# YGL_Y1.net
KiCad netlist of a schematic drawn in Altium Designer
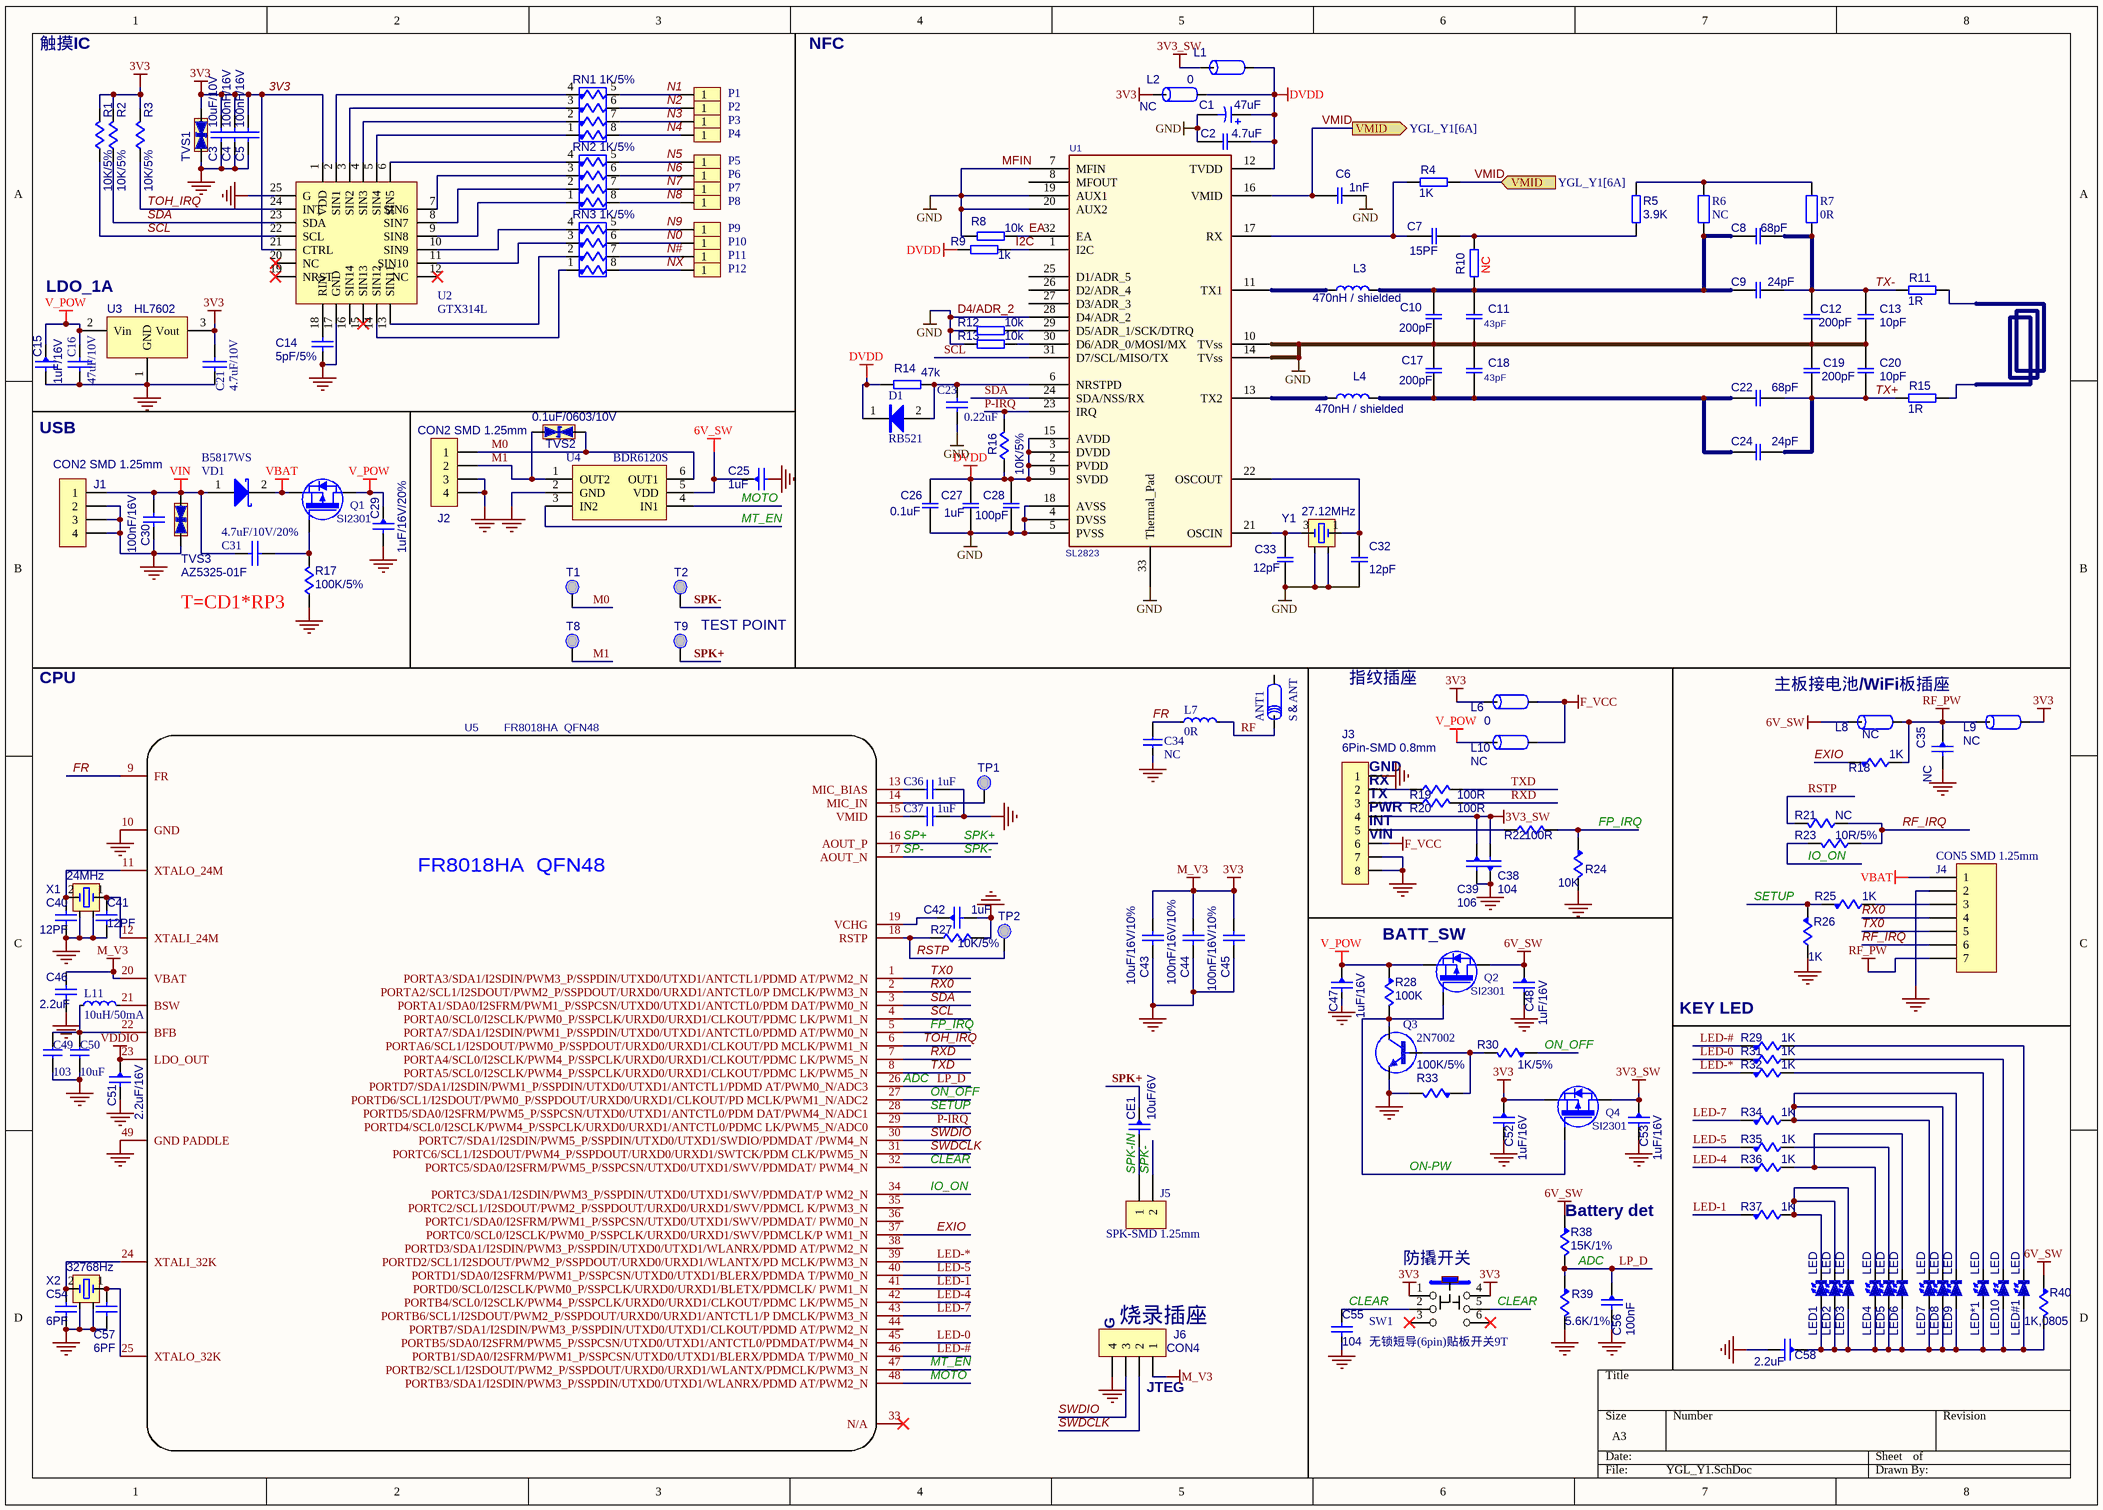
[diagram p0: YGL_Y1.SchDoc]

(export (version "E")
  (design (tool "Eeschema 10.0.6"))
  (components
    (comp (ref "ANT1") (value "S＆ANT") (footprint "ANT1206,SGM3157Y") (libsource (lib "TSL") (part "ANT")))
    (comp (ref "C1")
      (value "47uF")
      (footprint "C0603")
      (description "C_TANTAL_D")
      (fields (field (name "Comment") "330uF"))
      (libsource (lib "*") (part "C_TANTAL_D"))
    )
    (comp (ref "C2")
      (value "4.7uF")
      (footprint "C0603")
      (description "CAPC0603")
      (fields (field (name "Comment") "100nF"))
      (libsource (lib "*") (part "CAPC0603"))
    )
    (comp (ref "C3")
      (value "10uF/10V")
      (footprint "C0402")
      (description "Capacitor")
      (libsource (lib "") (part "CAP_1"))
    )
    (comp (ref "C4")
      (value "100nF/16V")
      (footprint "C0402")
      (description "Capacitor")
      (libsource (lib "") (part "CAP_1"))
    )
    (comp (ref "C5")
      (value "100nF/16V")
      (footprint "C0402")
      (description "Capacitor")
      (libsource (lib "") (part "CAP_1"))
    )
    (comp (ref "C6")
      (value "1nF")
      (footprint "C0402")
      (description "CAPC0603")
      (libsource (lib "*") (part "CAPC0603"))
    )
    (comp (ref "C7")
      (value "15PF")
      (footprint "C0402")
      (description "CAPC0805")
      (fields (field (name "Comment") "1nF"))
      (libsource (lib "*") (part "CAPC0805"))
    )
    (comp (ref "C8")
      (value "68pF")
      (footprint "C0402")
      (description "CAPC0805")
      (fields (field (name "Comment") "10pF"))
      (libsource (lib "*") (part "CAPC0805"))
    )
    (comp (ref "C9")
      (value "24pF")
      (footprint "C0402")
      (description "CAPC0805")
      (fields (field (name "Comment") "27pF"))
      (libsource (lib "*") (part "CAPC0805"))
    )
    (comp (ref "C10")
      (value "200pF")
      (footprint "C0402")
      (description "CAPC0805")
      (fields (field (name "Comment") "270pF"))
      (libsource (lib "*") (part "CAPC0805"))
    )
    (comp (ref "C11")
      (value "43pF")
      (footprint "C0402")
      (description "CAPC0805")
      (libsource (lib "*") (part "CAPC0805"))
    )
    (comp (ref "C12")
      (value "200pF")
      (footprint "C0402")
      (description "CAPC0805")
      (fields (field (name "Comment") "100pF"))
      (libsource (lib "*") (part "CAPC0805"))
    )
    (comp (ref "C13")
      (value "10pF")
      (footprint "C0402")
      (description "CAPC0805")
      (fields (field (name "Comment") "6pF"))
      (libsource (lib "*") (part "CAPC0805"))
    )
    (comp (ref "C14")
      (value "5pF/5%")
      (footprint "C0402")
      (description "Capacitor")
      (libsource (lib "") (part "CAP_1"))
    )
    (comp (ref "C15")
      (value "1uF/16V")
      (footprint "C0402")
      (description "Capacitor")
      (libsource (lib "VI-BC20X") (part "CAP"))
    )
    (comp (ref "C16")
      (value "47uF/10V")
      (footprint "C0402")
      (description "Capacitor")
      (libsource (lib "*") (part "CAP"))
    )
    (comp (ref "C17")
      (value "200pF")
      (footprint "C0402")
      (description "CAPC0805")
      (fields (field (name "Comment") "270pF"))
      (libsource (lib "*") (part "CAPC0805"))
    )
    (comp (ref "C18")
      (value "43pF")
      (footprint "C0402")
      (description "CAPC0805")
      (libsource (lib "*") (part "CAPC0805"))
    )
    (comp (ref "C19")
      (value "200pF")
      (footprint "C0402")
      (description "CAPC0805")
      (fields (field (name "Comment") "100pF"))
      (libsource (lib "*") (part "CAPC0805"))
    )
    (comp (ref "C20")
      (value "10pF")
      (footprint "C0402")
      (description "CAPC0805")
      (fields (field (name "Comment") "6pF"))
      (libsource (lib "*") (part "CAPC0805"))
    )
    (comp (ref "C21")
      (value "4.7uF/10V")
      (footprint "C0402")
      (description "Capacitor")
      (libsource (lib "*") (part "CAP"))
    )
    (comp (ref "C22")
      (value "68pF")
      (footprint "C0402")
      (description "CAPC0805")
      (fields (field (name "Comment") "27pF"))
      (libsource (lib "*") (part "CAPC0805"))
    )
    (comp (ref "C23")
      (value "0.22uF")
      (footprint "C0402")
      (description "Capacitor")
      (fields (field (name "Comment") "Cap") (field (name "PUBLISHER") "Altium Limited"))
      (libsource (lib "*") (part "Cap"))
    )
    (comp (ref "C24")
      (value "24pF")
      (footprint "C0402")
      (description "CAPC0805")
      (fields (field (name "Comment") "12pF"))
      (libsource (lib "*") (part "CAPC0805"))
    )
    (comp (ref "C25")
      (value "1uF")
      (footprint "C0402")
      (description "Capacitor")
      (libsource (lib "VI-BC20X") (part "CAP"))
    )
    (comp (ref "C26")
      (value "0.1uF")
      (footprint "C0402")
      (description "CAPC0603")
      (fields (field (name "Comment") "100nF"))
      (libsource (lib "*") (part "CAPC0603"))
    )
    (comp (ref "C27")
      (value "1uF")
      (footprint "C0402")
      (description "CAPC0603")
      (fields (field (name "Comment") "100nF"))
      (libsource (lib "*") (part "CAPC0603"))
    )
    (comp (ref "C28")
      (value "100pF")
      (footprint "C0402")
      (description "CAPC0603")
      (libsource (lib "*") (part "CAPC0603"))
    )
    (comp (ref "C29")
      (value "1uF/16V/20%")
      (footprint "C0402")
      (description "Capacitor")
      (libsource (lib "VI-BC20X") (part "CAP"))
    )
    (comp (ref "C30")
      (value "100nF/16V")
      (footprint "C0402")
      (description "Capacitor")
      (libsource (lib "") (part "CAP_1"))
    )
    (comp (ref "C31")
      (value "4.7uF/10V/20%")
      (footprint "C0402")
      (description "Capacitor")
      (libsource (lib "*") (part "CAP"))
    )
    (comp (ref "C32")
      (value "12pF")
      (footprint "C0402")
      (description "CAPC0603")
      (libsource (lib "*") (part "CAPC0603"))
    )
    (comp (ref "C33")
      (value "12pF")
      (footprint "C0402")
      (description "CAPC0603")
      (libsource (lib "*") (part "CAPC0603"))
    )
    (comp (ref "C34")
      (value "NC")
      (footprint "C0402")
      (description "Capacitor, NP0, ㊣5%")
      (fields (field (name "PART NUMBER") "C0402-0.8p") (field (name "PUBLISHER") "Nordic Semiconductor"))
      (libsource (lib "Nordic Passive DB") (part "CAP"))
    )
    (comp (ref "C35")
      (value "NC")
      (footprint "C0402")
      (description "Capacitor")
      (libsource (lib "VI-BC20X") (part "CAP"))
    )
    (comp (ref "C36")
      (value "1uF")
      (footprint "C0402")
      (description "Capacitor, NP0, ㊣5%")
      (fields (field (name "PART NUMBER") "C0402-0.8p") (field (name "PUBLISHER") "Nordic Semiconductor"))
      (libsource (lib "Nordic Passive DB") (part "CAP"))
    )
    (comp (ref "C37")
      (value "1uF")
      (footprint "C0402")
      (description "Capacitor, NP0, ㊣5%")
      (fields (field (name "PART NUMBER") "C0402-0.8p") (field (name "PUBLISHER") "Nordic Semiconductor"))
      (libsource (lib "Nordic Passive DB") (part "CAP"))
    )
    (comp (ref "C38")
      (value "104")
      (footprint "C0402")
      (description "Capacitor")
      (libsource (lib "VI-BC20X") (part "CAP"))
    )
    (comp (ref "C39")
      (value "106")
      (footprint "C0402")
      (description "Capacitor")
      (libsource (lib "VI-BC20X") (part "CAP"))
    )
    (comp (ref "C40")
      (value "12PF")
      (footprint "C0402")
      (description "Capacitor")
      (fields (field (name "PUBLISHER") "Altium Limited"))
      (libsource (lib "Miscellaneous Devices") (part "Cap"))
    )
    (comp (ref "C41")
      (value "12PF")
      (footprint "C0402")
      (description "Capacitor")
      (fields (field (name "PUBLISHER") "Altium Limited"))
      (libsource (lib "Miscellaneous Devices") (part "Cap"))
    )
    (comp (ref "C42")
      (value "1uF")
      (footprint "C0402")
      (description "Capacitor")
      (libsource (lib "VI-BC20X") (part "CAP"))
    )
    (comp (ref "C43")
      (value "10uF/16V/10%")
      (footprint "C0402")
      (description "Capacitor")
      (libsource (lib "") (part "CAP_1"))
    )
    (comp (ref "C44")
      (value "100nF/16V/10%")
      (footprint "C0402")
      (description "Capacitor")
      (libsource (lib "") (part "CAP_1"))
    )
    (comp (ref "C45")
      (value "100nF/16V/10%")
      (footprint "C0402")
      (description "Capacitor")
      (libsource (lib "") (part "CAP_1"))
    )
    (comp (ref "C46")
      (value "2.2uF")
      (footprint "C0402")
      (description "Capacitor")
      (fields (field (name "PUBLISHER") "Altium Limited"))
      (libsource (lib "Miscellaneous Devices") (part "Cap"))
    )
    (comp (ref "C47")
      (value "1uF/16V")
      (footprint "C0402")
      (description "Capacitor")
      (libsource (lib "VI-BC20X") (part "CAP"))
    )
    (comp (ref "C48")
      (value "1uF/16V")
      (footprint "C0402")
      (description "Capacitor")
      (libsource (lib "VI-BC20X") (part "CAP"))
    )
    (comp (ref "C49")
      (value "103")
      (footprint "C0402")
      (description "Capacitor, NP0, ㊣5%")
      (fields (field (name "PART NUMBER") "C0402-0.8p") (field (name "PUBLISHER") "Nordic Semiconductor"))
      (libsource (lib "Nordic Passive DB") (part "CAP"))
    )
    (comp (ref "C50")
      (value "10uF")
      (footprint "C0402")
      (description "Capacitor, NP0, ㊣5%")
      (fields (field (name "PART NUMBER") "C0402-0.8p") (field (name "PUBLISHER") "Nordic Semiconductor"))
      (libsource (lib "Nordic Passive DB") (part "CAP"))
    )
    (comp (ref "C51")
      (value "2.2uF/16V")
      (footprint "C0402")
      (description "Capacitor")
      (libsource (lib "VI-BC20X") (part "CAP"))
    )
    (comp (ref "C52")
      (value "1uF/16V")
      (footprint "C0402")
      (description "Capacitor")
      (libsource (lib "VI-BC20X") (part "CAP"))
    )
    (comp (ref "C53")
      (value "1uF/16V")
      (footprint "C0402")
      (description "Capacitor")
      (libsource (lib "VI-BC20X") (part "CAP"))
    )
    (comp (ref "C54")
      (value "6PF")
      (footprint "C0402")
      (description "Capacitor")
      (fields (field (name "PUBLISHER") "Altium Limited"))
      (libsource (lib "Miscellaneous Devices") (part "Cap"))
    )
    (comp (ref "C55")
      (value "104")
      (footprint "C0402")
      (description "Capacitor")
      (libsource (lib "") (part "CAP_1"))
    )
    (comp (ref "C56")
      (value "100nF")
      (footprint "C0402")
      (description "Capacitor")
      (libsource (lib "VI-BC20X") (part "CAP"))
    )
    (comp (ref "C57")
      (value "6PF")
      (footprint "C0402")
      (description "Capacitor")
      (fields (field (name "PUBLISHER") "Altium Limited"))
      (libsource (lib "Miscellaneous Devices") (part "Cap"))
    )
    (comp (ref "C58")
      (value "2.2uF")
      (footprint "C0402")
      (description "Capacitor")
      (libsource (lib "VI-BC20X") (part "CAP"))
    )
    (comp (ref "CE1")
      (value "10uF/6V")
      (footprint "C0402")
      (description "Capacitor")
      (libsource (lib "VI-BC20X") (part "CAP"))
    )
    (comp (ref "D1") (value "RB521") (footprint "SOD923") (libsource (lib "*") (part "DIODE-S")))
    (comp (ref "J1")
      (value "CON2 SMD 1.25mm")
      (footprint "SMD 1.25 2P")
      (description "Connector")
      (libsource (lib "NL-FLL00") (part "CON4"))
    )
    (comp (ref "J2")
      (value "CON2 SMD 1.25mm")
      (footprint "SMD 1.25 2P")
      (description "Connector")
      (libsource (lib "ND20D3") (part "CON4"))
    )
    (comp (ref "J3")
      (value "6Pin-SMD 0.8mm")
      (footprint "SMD 0.80 6P")
      (libsource (lib "TSL-600k-NFC触摸") (part "CON8"))
    )
    (comp (ref "J4")
      (value "CON5 SMD 1.25mm")
      (footprint "SMD 1.25 7P")
      (description "Header, 7-Pin")
      (fields (field (name "PUBLISHER") "Altium Limited"))
      (libsource (lib "Miscellaneous Connectors") (part "Header 7"))
    )
    (comp (ref "J5")
      (value "SPK-SMD 1.25mm")
      (footprint "SMD 1.25 2P")
      (description "Connector")
      (libsource (lib "*") (part "CON2"))
    )
    (comp (ref "J6")
      (value "CON4")
      (footprint "SMD 1.25 4p")
      (description "Connector")
      (libsource (lib "") (part "CON4_1"))
    )
    (comp (ref "L1") (value "0") (footprint "L0603") (libsource (lib "*") (part "FB")))
    (comp (ref "L2") (value "NC") (footprint "L0603") (libsource (lib "*") (part "FB")))
    (comp (ref "L3")
      (value "470nH / shielded")
      (footprint "L0603")
      (description "INDC1812")
      (fields (field (name "Comment") "470nH / shielded (1210)"))
      (libsource (lib "*") (part "INDC1812"))
    )
    (comp (ref "L4")
      (value "470nH / shielded")
      (footprint "L0603")
      (description "INDC1812")
      (fields (field (name "Comment") "470nH / shielded (1210)"))
      (libsource (lib "*") (part "INDC1812"))
    )
    (comp (ref "L6") (value "0") (footprint "L0603") (libsource (lib "*") (part "FB")))
    (comp (ref "L7")
      (value "0R")
      (footprint "L0603")
      (description "High frequency chip inductor ㊣5%")
      (fields (field (name "PART NUMBER") "L0402-3n9") (field (name "PUBLISHER") "Nordic Semiconductor"))
      (libsource (lib "Nordic Passive DB") (part "IND"))
    )
    (comp (ref "L8") (value "NC") (footprint "L0603") (libsource (lib "*") (part "FB")))
    (comp (ref "L9") (value "NC") (footprint "L0603") (libsource (lib "*") (part "FB")))
    (comp (ref "L10") (value "NC") (footprint "L0603") (libsource (lib "*") (part "FB")))
    (comp (ref "L11")
      (value "10uH/50mA")
      (footprint "L0603")
      (description "High frequency chip inductor ㊣5%")
      (fields (field (name "PART NUMBER") "L0402-3n9") (field (name "PUBLISHER") "Nordic Semiconductor"))
      (libsource (lib "Nordic Passive DB") (part "IND"))
    )
    (comp (ref "LED#1") (value "LED") (footprint "LED/1206") (libsource (lib "SCH") (part "LED")))
    (comp (ref "LED*1") (value "LED") (footprint "LED/1206") (libsource (lib "SCH") (part "LED")))
    (comp (ref "LED1") (value "LED") (footprint "LED/1206") (libsource (lib "SCH") (part "LED")))
    (comp (ref "LED2") (value "LED") (footprint "LED/1206") (libsource (lib "SCH") (part "LED")))
    (comp (ref "LED3") (value "LED") (footprint "LED/1206") (libsource (lib "SCH") (part "LED")))
    (comp (ref "LED4") (value "LED") (footprint "LED/1206") (libsource (lib "SCH") (part "LED")))
    (comp (ref "LED5") (value "LED") (footprint "LED/1206") (libsource (lib "SCH") (part "LED")))
    (comp (ref "LED6") (value "LED") (footprint "LED/1206") (libsource (lib "SCH") (part "LED")))
    (comp (ref "LED7") (value "LED") (footprint "LED/1206") (libsource (lib "SCH") (part "LED")))
    (comp (ref "LED8") (value "LED") (footprint "LED/1206") (libsource (lib "SCH") (part "LED")))
    (comp (ref "LED9") (value "LED") (footprint "LED/1206") (libsource (lib "SCH") (part "LED")))
    (comp (ref "LED10") (value "LED") (footprint "LED/1206") (libsource (lib "SCH") (part "LED")))
    (comp (ref "P1")
      (value "CON1")
      (footprint "TEST 0.8")
      (description "Connector")
      (libsource (lib "*") (part "CON1"))
    )
    (comp (ref "P2")
      (value "CON1")
      (footprint "TEST 0.8")
      (description "Connector")
      (libsource (lib "*") (part "CON1"))
    )
    (comp (ref "P3")
      (value "CON1")
      (footprint "TEST 0.8")
      (description "Connector")
      (libsource (lib "*") (part "CON1"))
    )
    (comp (ref "P4")
      (value "CON1")
      (footprint "TEST 0.8")
      (description "Connector")
      (libsource (lib "*") (part "CON1"))
    )
    (comp (ref "P5")
      (value "CON1")
      (footprint "TEST 0.8")
      (description "Connector")
      (libsource (lib "*") (part "CON1"))
    )
    (comp (ref "P6")
      (value "CON1")
      (footprint "TEST 0.8")
      (description "Connector")
      (libsource (lib "*") (part "CON1"))
    )
    (comp (ref "P7")
      (value "CON1")
      (footprint "TEST 0.8")
      (description "Connector")
      (libsource (lib "*") (part "CON1"))
    )
    (comp (ref "P8")
      (value "CON1")
      (footprint "TEST 0.8")
      (description "Connector")
      (libsource (lib "*") (part "CON1"))
    )
    (comp (ref "P9")
      (value "CON1")
      (footprint "TEST 0.8")
      (description "Connector")
      (libsource (lib "*") (part "CON1"))
    )
    (comp (ref "P10")
      (value "CON1")
      (footprint "TEST 0.8")
      (description "Connector")
      (libsource (lib "*") (part "CON1"))
    )
    (comp (ref "P11")
      (value "CON1")
      (footprint "TEST 0.8")
      (description "Connector")
      (libsource (lib "*") (part "CON1"))
    )
    (comp (ref "P12")
      (value "CON1")
      (footprint "TEST 0.8")
      (description "Connector")
      (libsource (lib "*") (part "CON1"))
    )
    (comp (ref "Q1")
      (value "SI2301")
      (footprint "SOT-23-3_L2.9-W1.6-P1.90-LS2.8-BR")
      (libsource (lib "NL-FLL19A _V1.0") (part "MOSFET-P"))
    )
    (comp (ref "Q2")
      (value "SI2301")
      (footprint "SOT-23-3_L2.9-W1.6-P1.90-LS2.8-BR")
      (libsource (lib "NL-FLL19A _V1.0") (part "MOSFET-P"))
    )
    (comp (ref "Q3")
      (value "2N7002")
      (footprint "SOT-23-3_L2.9-W1.6-P1.90-LS2.8-BR")
      (libsource (lib "*") (part "NPN"))
    )
    (comp (ref "Q4")
      (value "SI2301")
      (footprint "SOT-23-3_L2.9-W1.6-P1.90-LS2.8-BR")
      (libsource (lib "NL-FLL19A _V1.0") (part "MOSFET-P"))
    )
    (comp (ref "R1") (value "10K/5%") (footprint "R0402") (libsource (lib "NL-FLL00") (part "RES1")))
    (comp (ref "R2") (value "10K/5%") (footprint "R0402") (libsource (lib "NL-FLL00") (part "RES1")))
    (comp (ref "R3") (value "10K/5%") (footprint "R0402") (libsource (lib "NL-FLL00") (part "RES1")))
    (comp (ref "R4")
      (value "1K")
      (footprint "R0402")
      (description "RESC0805")
      (fields (field (name "Comment") "160R"))
      (libsource (lib "*") (part "RESC0805"))
    )
    (comp (ref "R5")
      (value "3.9K")
      (footprint "R0402")
      (description "RESC0805")
      (fields (field (name "Comment") "2k4"))
      (libsource (lib "*") (part "RESC0805"))
    )
    (comp (ref "R6")
      (value "16.9")
      (footprint "R0402")
      (description "0")
      (fields (field (name "ALTIUM_UNNAMED_1") "NC") (field (name "PUBLISHER") "Altium Limited"))
      (libsource (lib "ETC-Test1-1") (part "Res2"))
    )
    (comp (ref "R7")
      (value "16.9")
      (footprint "R0402")
      (description "0")
      (fields (field (name "ALTIUM_UNNAMED_1") "0R") (field (name "PUBLISHER") "Altium Limited"))
      (libsource (lib "ETC-Test1-1") (part "Res2"))
    )
    (comp (ref "R8")
      (value "10k")
      (footprint "R0402")
      (description "RESC0805")
      (libsource (lib "*") (part "RESC0805"))
    )
    (comp (ref "R9")
      (value "1k")
      (footprint "R0402")
      (description "RESC0805")
      (fields (field (name "Comment") "10k"))
      (libsource (lib "*") (part "RESC0805"))
    )
    (comp (ref "R10")
      (value "NC")
      (footprint "R0402")
      (description "RESC0805")
      (libsource (lib "*") (part "RESC0805"))
    )
    (comp (ref "R11")
      (value "1R")
      (footprint "R0402")
      (description "RESC0805")
      (fields (field (name "Comment") "160R"))
      (libsource (lib "*") (part "RESC0805"))
    )
    (comp (ref "R12")
      (value "10k")
      (footprint "R0402")
      (description "RESC0805")
      (libsource (lib "*") (part "RESC0805"))
    )
    (comp (ref "R13")
      (value "10k")
      (footprint "R0402")
      (description "RESC0805")
      (libsource (lib "*") (part "RESC0805"))
    )
    (comp (ref "R14")
      (value "47k")
      (footprint "R0402")
      (description "RESC0805")
      (fields (field (name "Comment") "10k"))
      (libsource (lib "*") (part "RESC0805"))
    )
    (comp (ref "R15")
      (value "1R")
      (footprint "R0402")
      (description "RESC0805")
      (fields (field (name "Comment") "160R"))
      (libsource (lib "*") (part "RESC0805"))
    )
    (comp (ref "R16") (value "10K/5%") (footprint "R0402") (libsource (lib "NL-FLL00") (part "RES1")))
    (comp (ref "R17") (value "100K/5%") (footprint "R0402") (libsource (lib "NL-FLL00") (part "RES1")))
    (comp (ref "R18") (value "1K") (footprint "R0402") (libsource (lib "智能拉手门禁_V2.0") (part "RES1")))
    (comp (ref "R19") (value "100R") (footprint "R0402") (libsource (lib "NL-FLL00") (part "RES1")))
    (comp (ref "R20") (value "100R") (footprint "R0402") (libsource (lib "NL-FLL00") (part "RES1")))
    (comp (ref "R21") (value "NC") (footprint "R0402") (libsource (lib "NL-FLL00") (part "RES1")))
    (comp (ref "R22") (value "100R") (footprint "R0402") (libsource (lib "NL-FLL00") (part "RES1")))
    (comp (ref "R23") (value "10R/5%") (footprint "R0402") (libsource (lib "NL-FLL00") (part "RES1")))
    (comp (ref "R24") (value "10K") (footprint "R0402") (libsource (lib "智能拉手门禁_V2.0") (part "RES1")))
    (comp (ref "R25") (value "1K") (footprint "R0402") (libsource (lib "智能拉手门禁_V2.0") (part "RES1")))
    (comp (ref "R26") (value "1K") (footprint "R0402") (libsource (lib "智能拉手门禁_V2.0") (part "RES1")))
    (comp (ref "R27") (value "10K/5%") (footprint "R0402") (libsource (lib "NL-FLL00") (part "RES1")))
    (comp (ref "R28") (value "100K") (footprint "R0402") (libsource (lib "智能拉手门禁_V2.0") (part "RES1")))
    (comp (ref "R29") (value "1K") (footprint "R0402") (libsource (lib "智能拉手门禁_V2.0") (part "RES1")))
    (comp (ref "R30") (value "1K/5%") (footprint "R0402") (libsource (lib "智能拉手门禁_V2.0") (part "RES1")))
    (comp (ref "R31") (value "1K") (footprint "R0402") (libsource (lib "智能拉手门禁_V2.0") (part "RES1")))
    (comp (ref "R32") (value "1K") (footprint "R0402") (libsource (lib "智能拉手门禁_V2.0") (part "RES1")))
    (comp (ref "R33") (value "100K/5%") (footprint "R0402") (libsource (lib "智能拉手门禁_V2.0") (part "RES1")))
    (comp (ref "R34") (value "1K") (footprint "R0402") (libsource (lib "智能拉手门禁_V2.0") (part "RES1")))
    (comp (ref "R35") (value "1K") (footprint "R0402") (libsource (lib "智能拉手门禁_V2.0") (part "RES1")))
    (comp (ref "R36") (value "1K") (footprint "R0402") (libsource (lib "智能拉手门禁_V2.0") (part "RES1")))
    (comp (ref "R37") (value "1K") (footprint "R0402") (libsource (lib "智能拉手门禁_V2.0") (part "RES1")))
    (comp (ref "R38") (value "15K/1%") (footprint "R0402") (libsource (lib "智能拉手门禁_V2.0") (part "RES1")))
    (comp (ref "R39") (value "5.6K/1%") (footprint "R0402") (libsource (lib "智能拉手门禁_V2.0") (part "RES1")))
    (comp (ref "R40") (value "1K,0805") (footprint "R0402") (libsource (lib "智能拉手门禁_V2.0") (part "RES1")))
    (comp (ref "RN1")
      (value "1K/5%")
      (footprint "R4D02")
      (libsource (lib "VI-LSX0X(拉手门禁)_V2.0") (part "8P4R-0603"))
    )
    (comp (ref "RN2")
      (value "1K/5%")
      (footprint "R4D02")
      (libsource (lib "VI-LSX0X(拉手门禁)_V2.0") (part "8P4R-0603"))
    )
    (comp (ref "RN3")
      (value "1K/5%")
      (footprint "R4D02")
      (libsource (lib "VI-LSX0X(拉手门禁)_V2.0") (part "8P4R-0603"))
    )
    (comp (ref "SW1")
      (value "无锁短导(6pin)贴板开关9T")
      (footprint "SW-6P-5.8X5.8_SMD")
      (libsource (lib "PCD3D_ID811B") (part "SW-4T"))
    )
    (comp (ref "T1")
      (value "~")
      (footprint "TEST 0.8")
      (description "Capacitor")
      (libsource (lib "*") (part "TX"))
    )
    (comp (ref "T2")
      (value "~")
      (footprint "TEST 0.8")
      (description "Capacitor")
      (libsource (lib "*") (part "TX"))
    )
    (comp (ref "T8")
      (value "~")
      (footprint "TEST 0.8")
      (description "Capacitor")
      (libsource (lib "*") (part "TX"))
    )
    (comp (ref "T9")
      (value "~")
      (footprint "TEST 0.8")
      (description "Capacitor")
      (libsource (lib "*") (part "TX"))
    )
    (comp (ref "TP1")
      (value "~")
      (footprint "TEST 0.8")
      (description "Capacitor")
      (libsource (lib "*") (part "TX"))
    )
    (comp (ref "TP2")
      (value "~")
      (footprint "TEST 0.8")
      (description "Capacitor")
      (libsource (lib "*") (part "TX"))
    )
    (comp (ref "TVS1")
      (value "AZ5325-01F")
      (footprint "SOD-323_L1.8-W1.3-LS2.5-RD")
      (libsource (lib "NL-FLL19D") (part "ESD"))
    )
    (comp (ref "TVS2")
      (value "0.1uF/0603/10V")
      (footprint "SOD-323_L1.8-W1.3-LS2.5-RD")
      (libsource (lib "") (part "ESD_1"))
    )
    (comp (ref "TVS3")
      (value "AZ5325-01F")
      (footprint "SOD-323_L1.8-W1.3-LS2.5-RD")
      (libsource (lib "NL-FLL19D") (part "ESD"))
    )
    (comp (ref "U1")
      (value "SL2823")
      (footprint "Z_QFN50P500X500X100-32N")
      (description "SL2523")
      (libsource (lib "ETC-Test1-1") (part "SL2523"))
    )
    (comp (ref "U2")
      (value "GTX314L")
      (footprint "QFN24_0.5 - U2")
      (libsource (lib "NL-FLL19C") (part "GTX314L"))
    )
    (comp (ref "U3")
      (value "HL7602")
      (footprint "SOT-89_L4.5-W2.5-P1.50-LS4.2-BR")
      (libsource (lib "*") (part "VOLTREG_4P"))
    )
    (comp (ref "U4")
      (value "BDR6120S")
      (footprint "SOT-23-6_L2.9-W1.6-P0.95-LS2.8-BL")
      (libsource (lib "*") (part "MX116L"))
    )
    (comp (ref "U5")
      (value "FR8018HA  QFN48")
      (footprint "QFN48_6*6*0.75_P0.4")
      (fields (field (name "CONTRIBUTOR") "liaobin123"))
      (libsource (lib "altium-import") (part "root_0_FR8018HA  QFN48_"))
    )
    (comp (ref "VD1")
      (value "B5817WS")
      (footprint "SOD-323_L1.8-W1.3-LS2.5-RD")
      (libsource (lib "*") (part "RB521"))
    )
    (comp (ref "X1")
      (value "24MHz")
      (footprint "XTAL-3225-SMT-A")
      (libsource (lib "SCH_1") (part "CRYSTAL_4PIN"))
    )
    (comp (ref "X2")
      (value "32768Hz")
      (footprint "XTAL_FC-135$2F$3215")
      (libsource (lib "SCH_1") (part "CRYSTAL_4PIN"))
    )
    (comp (ref "Y1")
      (value "27.12MHz")
      (footprint "XTAL-3225-SMT-A")
      (libsource (lib "NM810A_R1") (part "CRYSTAL_4PIN"))
    )
  )
  (nets
    (net (code "1") (name "/ADC") (class "Default")
      (node (ref "C56") (pin "1") (pinfunction "1_1") (pintype "passive"))
      (node (ref "R38") (pin "2") (pinfunction "2_2") (pintype "passive"))
      (node (ref "R39") (pin "1") (pinfunction "1_1") (pintype "passive"))
      (node (ref "U5") (pin "26") (pinfunction "PORTD7/SDA1/I2SDIN/PWM1_P/SSPDIN/UTXD0/UTXD1/ANTCTL1/PDMD_AT/PWM0_N/ADC3_26") (pintype "passive"))
    )
    (net (code "2") (name "/CLEAR") (class "Default")
      (node (ref "C55") (pin "1") (pinfunction "1_1") (pintype "passive"))
      (node (ref "SW1") (pin "2") (pinfunction "2_2") (pintype "passive"))
      (node (ref "SW1") (pin "5") (pinfunction "5_5") (pintype "passive"))
      (node (ref "U5") (pin "32") (pinfunction "PORTC5/SDA0/I2SFRM/PWM5_P/SSPCSN/UTXD0/UTXD1/SWV/PDMDAT/_PWM4_N_32") (pintype "passive"))
    )
    (net (code "3") (name "/EA") (class "Default")
      (node (ref "R8") (pin "2") (pintype "passive"))
      (node (ref "U1") (pin "32") (pinfunction "EA_32") (pintype "passive"))
    )
    (net (code "4") (name "/EXIO") (class "Default")
      (node (ref "R18") (pin "1") (pinfunction "1_1") (pintype "passive"))
      (node (ref "U5") (pin "37") (pinfunction "PORTC0/SCL0/I2SCLK/PWM0_P/SSPCLK/URXD0/URXD1/SWV/PDMCLK/P_WM1_N_37") (pintype "passive"))
    )
    (net (code "5") (name "/FP_IRQ") (class "Default")
      (node (ref "R22") (pin "1") (pinfunction "1_1") (pintype "passive"))
      (node (ref "R24") (pin "1") (pinfunction "1_1") (pintype "passive"))
      (node (ref "U5") (pin "5") (pinfunction "PORTA7/SDA1/I2SDIN/PWM1_P/SSPDIN/UTXD0/UTXD1/ANTCTL0/PDMD_AT/PWM0_N_5") (pintype "passive"))
    )
    (net (code "6") (name "/FR") (class "Default")
      (node (ref "C34") (pin "2") (pinfunction "2_2") (pintype "passive"))
      (node (ref "L7") (pin "1") (pinfunction "1_1") (pintype "passive"))
      (node (ref "U5") (pin "9") (pinfunction "FR_9") (pintype "passive"))
    )
    (net (code "7") (name "/I2C") (class "Default")
      (node (ref "R9") (pin "2") (pintype "passive"))
      (node (ref "U1") (pin "1") (pinfunction "I2C_1") (pintype "passive"))
    )
    (net (code "8") (name "/IO_ON") (class "Default")
      (node (ref "R23") (pin "2") (pinfunction "2_2") (pintype "passive"))
      (node (ref "U5") (pin "34") (pinfunction "PORTC3/SDA1/I2SDIN/PWM3_P/SSPDIN/UTXD0/UTXD1/SWV/PDMDAT/P_WM2_N_34") (pintype "passive"))
    )
    (net (code "9") (name "/LED-#") (class "Default")
      (node (ref "R29") (pin "1") (pinfunction "1_1") (pintype "passive"))
      (node (ref "U5") (pin "46") (pinfunction "PORTB1/SDA0/I2SFRM/PWM1_P/SSPCSN/UTXD0/UTXD1/BLERX/PDMDA_T/PWM0_N_46") (pintype "passive"))
    )
    (net (code "10") (name "/LED-*") (class "Default")
      (node (ref "R32") (pin "1") (pinfunction "1_1") (pintype "passive"))
      (node (ref "U5") (pin "39") (pinfunction "PORTD2/SCL1/I2SDOUT/PWM2_P/SSPDOUT/URXD0/URXD1/WLANTX/PD_MCLK/PWM3_N_39") (pintype "passive"))
    )
    (net (code "11") (name "/LED-0") (class "Default")
      (node (ref "R31") (pin "1") (pinfunction "1_1") (pintype "passive"))
      (node (ref "U5") (pin "45") (pinfunction "PORTB5/SDA0/I2SFRM/PWM5_P/SSPCSN/UTXD0/UTXD1/ANTCTL0/PDMDAT/PWM4_N_45") (pintype "passive"))
    )
    (net (code "12") (name "/LED-1") (class "Default")
      (node (ref "R37") (pin "1") (pinfunction "1_1") (pintype "passive"))
      (node (ref "U5") (pin "41") (pinfunction "PORTD0/SCL0/I2SCLK/PWM0_P/SSPCLK/URXD0/URXD1/BLETX/PDMCLK/_PWM1_N_41") (pintype "passive"))
    )
    (net (code "13") (name "/LED-4") (class "Default")
      (node (ref "R36") (pin "1") (pinfunction "1_1") (pintype "passive"))
      (node (ref "U5") (pin "42") (pinfunction "PORTB4/SCL0/I2SCLK/PWM4_P/SSPCLK/URXD0/URXD1/CLKOUT/PDMC_LK/PWM5_N_42") (pintype "passive"))
    )
    (net (code "14") (name "/LED-5") (class "Default")
      (node (ref "R35") (pin "1") (pinfunction "1_1") (pintype "passive"))
      (node (ref "U5") (pin "40") (pinfunction "PORTD1/SDA0/I2SFRM/PWM1_P/SSPCSN/UTXD0/UTXD1/BLERX/PDMDA_T/PWM0_N_40") (pintype "passive"))
    )
    (net (code "15") (name "/LED-7") (class "Default")
      (node (ref "R34") (pin "1") (pinfunction "1_1") (pintype "passive"))
      (node (ref "U5") (pin "43") (pinfunction "PORTB6/SCL1/I2SDOUT/PWM2_P/SSPDOUT/URXD0/URXD1/ANTCTL1/P_DMCLK/PWM3_N_43") (pintype "passive"))
    )
    (net (code "16") (name "/M0") (class "Default")
      (node (ref "J2") (pin "1") (pinfunction "1_1") (pintype "passive"))
      (node (ref "T1") (pin "1") (pinfunction "1_1") (pintype "passive"))
      (node (ref "TVS2") (pin "2") (pinfunction "2_2") (pintype "passive"))
      (node (ref "U4") (pin "6") (pinfunction "OUT1_6") (pintype "passive"))
    )
    (net (code "17") (name "/M1") (class "Default")
      (node (ref "J2") (pin "2") (pinfunction "2_2") (pintype "passive"))
      (node (ref "T8") (pin "1") (pinfunction "1_1") (pintype "passive"))
      (node (ref "TVS2") (pin "1") (pinfunction "1_1") (pintype "passive"))
      (node (ref "U4") (pin "1") (pinfunction "OUT2_1") (pintype "passive"))
    )
    (net (code "18") (name "/MOTO") (class "Default")
      (node (ref "U4") (pin "4") (pinfunction "IN1_4") (pintype "passive"))
      (node (ref "U5") (pin "48") (pinfunction "PORTB3/SDA1/I2SDIN/PWM3_P/SSPDIN/UTXD0/UTXD1/WLANRX/PDMD_AT/PWM2_N_48") (pintype "passive"))
    )
    (net (code "19") (name "/MT_EN") (class "Default")
      (node (ref "U4") (pin "3") (pinfunction "IN2_3") (pintype "passive"))
      (node (ref "U5") (pin "47") (pinfunction "PORTB2/SCL1/I2SDOUT/PWM2_P/SSPDOUT/URXD0/URXD1/WLANTX/PDMCLK/PWM3_N_47") (pintype "passive"))
    )
    (net (code "20") (name "/N#") (class "Default")
      (node (ref "P11") (pin "1") (pinfunction "1_1") (pintype "passive"))
      (node (ref "RN3") (pin "7") (pinfunction "7_7") (pintype "passive"))
    )
    (net (code "21") (name "/N0") (class "Default")
      (node (ref "P10") (pin "1") (pinfunction "1_1") (pintype "passive"))
      (node (ref "RN3") (pin "6") (pinfunction "6_6") (pintype "passive"))
    )
    (net (code "22") (name "/N1") (class "Default")
      (node (ref "P1") (pin "1") (pinfunction "1_1") (pintype "passive"))
      (node (ref "RN1") (pin "5") (pinfunction "5_5") (pintype "passive"))
    )
    (net (code "23") (name "/N2") (class "Default")
      (node (ref "P2") (pin "1") (pinfunction "1_1") (pintype "passive"))
      (node (ref "RN1") (pin "6") (pinfunction "6_6") (pintype "passive"))
    )
    (net (code "24") (name "/N3") (class "Default")
      (node (ref "P3") (pin "1") (pinfunction "1_1") (pintype "passive"))
      (node (ref "RN1") (pin "7") (pinfunction "7_7") (pintype "passive"))
    )
    (net (code "25") (name "/N4") (class "Default")
      (node (ref "P4") (pin "1") (pinfunction "1_1") (pintype "passive"))
      (node (ref "RN1") (pin "8") (pinfunction "8_8") (pintype "passive"))
    )
    (net (code "26") (name "/N5") (class "Default")
      (node (ref "P5") (pin "1") (pinfunction "1_1") (pintype "passive"))
      (node (ref "RN2") (pin "5") (pinfunction "5_5") (pintype "passive"))
    )
    (net (code "27") (name "/N6") (class "Default")
      (node (ref "P6") (pin "1") (pinfunction "1_1") (pintype "passive"))
      (node (ref "RN2") (pin "6") (pinfunction "6_6") (pintype "passive"))
    )
    (net (code "28") (name "/N7") (class "Default")
      (node (ref "P7") (pin "1") (pinfunction "1_1") (pintype "passive"))
      (node (ref "RN2") (pin "7") (pinfunction "7_7") (pintype "passive"))
    )
    (net (code "29") (name "/N8") (class "Default")
      (node (ref "P8") (pin "1") (pinfunction "1_1") (pintype "passive"))
      (node (ref "RN2") (pin "8") (pinfunction "8_8") (pintype "passive"))
    )
    (net (code "30") (name "/N9") (class "Default")
      (node (ref "P9") (pin "1") (pinfunction "1_1") (pintype "passive"))
      (node (ref "RN3") (pin "5") (pinfunction "5_5") (pintype "passive"))
    )
    (net (code "31") (name "/NX") (class "Default")
      (node (ref "P12") (pin "1") (pinfunction "1_1") (pintype "passive"))
      (node (ref "RN3") (pin "8") (pinfunction "8_8") (pintype "passive"))
    )
    (net (code "32") (name "/ON-PW") (class "Default")
      (node (ref "Q2") (pin "1") (pinfunction "G_1") (pintype "passive"))
      (node (ref "Q3") (pin "3") (pinfunction "C_3") (pintype "passive"))
      (node (ref "Q4") (pin "1") (pinfunction "G_1") (pintype "passive"))
      (node (ref "R28") (pin "2") (pinfunction "2_2") (pintype "passive"))
    )
    (net (code "33") (name "/ON_OFF") (class "Default")
      (node (ref "R30") (pin "1") (pinfunction "1_1") (pintype "passive"))
      (node (ref "U5") (pin "27") (pinfunction "PORTD6/SCL1/I2SDOUT/PWM0_P/SSPDOUT/URXD0/URXD1/CLKOUT/PD_MCLK/PWM1_N/ADC2_27") (pintype "passive"))
    )
    (net (code "34") (name "/P-IRQ") (class "Default")
      (node (ref "R16") (pin "2") (pinfunction "2_2") (pintype "passive"))
      (node (ref "U1") (pin "23") (pinfunction "IRQ_23") (pintype "passive"))
      (node (ref "U5") (pin "29") (pinfunction "PORTD4/SCL0/I2SCLK/PWM4_P/SSPCLK/URXD0/URXD1/ANTCTL0/PDMC_LK/PWM5_N/ADC0_29") (pintype "passive"))
    )
    (net (code "35") (name "/RF") (class "Default")
      (node (ref "ANT1") (pin "1") (pintype "passive"))
      (node (ref "L7") (pin "2") (pinfunction "2_2") (pintype "passive"))
    )
    (net (code "36") (name "/RF_IRQ") (class "Default")
      (node (ref "J4") (pin "6") (pinfunction "6_6") (pintype "passive"))
      (node (ref "R21") (pin "1") (pinfunction "1_1") (pintype "passive"))
      (node (ref "R23") (pin "1") (pinfunction "1_1") (pintype "passive"))
    )
    (net (code "37") (name "/RSTP") (class "Default")
      (node (ref "R21") (pin "2") (pinfunction "2_2") (pintype "passive"))
      (node (ref "R27") (pin "1") (pinfunction "1_1") (pintype "passive"))
      (node (ref "TP2") (pin "1") (pinfunction "1_1") (pintype "passive"))
      (node (ref "U5") (pin "18") (pinfunction "RSTP_18") (pintype "passive"))
    )
    (net (code "38") (name "/RX0") (class "Default")
      (node (ref "J4") (pin "4") (pinfunction "4_4") (pintype "passive"))
      (node (ref "U5") (pin "2") (pinfunction "PORTA2/SCL1/I2SDOUT/PWM2_P/SSPDOUT/URXD0/URXD1/ANTCTL0/P_DMCLK/PWM3_N_2") (pintype "passive"))
    )
    (net (code "39") (name "/RXD") (class "Default")
      (node (ref "R20") (pin "2") (pinfunction "2_2") (pintype "passive"))
      (node (ref "U5") (pin "7") (pinfunction "PORTA4/SCL0/I2SCLK/PWM4_P/SSPCLK/URXD0/URXD1/CLKOUT/PDMC_LK/PWM5_N_7") (pintype "passive"))
    )
    (net (code "40") (name "/SCL") (class "Default")
      (node (ref "R1") (pin "1") (pinfunction "1_1") (pintype "passive"))
      (node (ref "U1") (pin "31") (pinfunction "D7/SCL/MISO/TX_31") (pintype "passive"))
      (node (ref "U2") (pin "22") (pinfunction "SCL_22") (pintype "passive"))
      (node (ref "U5") (pin "4") (pinfunction "PORTA0/SCL0/I2SCLK/PWM0_P/SSPCLK/URXD0/URXD1/CLKOUT/PDMC_LK/PWM1_N_4") (pintype "passive"))
    )
    (net (code "41") (name "/SDA") (class "Default")
      (node (ref "R2") (pin "1") (pinfunction "1_1") (pintype "passive"))
      (node (ref "U1") (pin "24") (pinfunction "SDA/NSS/RX_24") (pintype "passive"))
      (node (ref "U2") (pin "23") (pinfunction "SDA_23") (pintype "passive"))
      (node (ref "U5") (pin "3") (pinfunction "PORTA1/SDA0/I2SFRM/PWM1_P/SSPCSN/UTXD0/UTXD1/ANTCTL0/PDM_DAT/PWM0_N_3") (pintype "passive"))
    )
    (net (code "42") (name "/SETUP") (class "Default")
      (node (ref "R25") (pin "1") (pinfunction "1_1") (pintype "passive"))
      (node (ref "R26") (pin "1") (pinfunction "1_1") (pintype "passive"))
      (node (ref "U5") (pin "28") (pinfunction "PORTD5/SDA0/I2SFRM/PWM5_P/SSPCSN/UTXD0/UTXD1/ANTCTL0/PDM_DAT/PWM4_N/ADC1_28") (pintype "passive"))
    )
    (net (code "43") (name "/SP+") (class "Default")
      (node (ref "CE1") (pin "1") (pinfunction "1_1") (pintype "passive"))
      (node (ref "T9") (pin "1") (pinfunction "1_1") (pintype "passive"))
      (node (ref "U5") (pin "16") (pinfunction "AOUT_P_16") (pintype "passive"))
    )
    (net (code "44") (name "/SP-") (class "Default")
      (node (ref "J5") (pin "2") (pinfunction "2_2") (pintype "passive"))
      (node (ref "T2") (pin "1") (pinfunction "1_1") (pintype "passive"))
      (node (ref "U5") (pin "17") (pinfunction "AOUT_N_17") (pintype "passive"))
    )
    (net (code "45") (name "/SPK-IN") (class "Default")
      (node (ref "CE1") (pin "2") (pinfunction "2_2") (pintype "passive"))
      (node (ref "J5") (pin "1") (pinfunction "1_1") (pintype "passive"))
    )
    (net (code "46") (name "/SWDCLK") (class "Default")
      (node (ref "J6") (pin "2") (pinfunction "2_2") (pintype "passive"))
      (node (ref "U5") (pin "31") (pinfunction "PORTC6/SCL1/I2SDOUT/PWM4_P/SSPDOUT/URXD0/URXD1/SWTCK/PDM_CLK/PWM5_N_31") (pintype "passive"))
    )
    (net (code "47") (name "/SWDIO") (class "Default")
      (node (ref "J6") (pin "3") (pinfunction "3_3") (pintype "passive"))
      (node (ref "U5") (pin "30") (pinfunction "PORTC7/SDA1/I2SDIN/PWM5_P/SSPDIN/UTXD0/UTXD1/SWDIO/PDMDAT_/PWM4_N_30") (pintype "passive"))
    )
    (net (code "48") (name "/TOH_IRQ") (class "Default")
      (node (ref "R3") (pin "1") (pinfunction "1_1") (pintype "passive"))
      (node (ref "U2") (pin "24") (pinfunction "INT_24") (pintype "passive"))
      (node (ref "U5") (pin "6") (pinfunction "PORTA6/SCL1/I2SDOUT/PWM0_P/SSPDOUT/URXD0/URXD1/CLKOUT/PD_MCLK/PWM1_N_6") (pintype "passive"))
    )
    (net (code "49") (name "/TX+") (class "Default")
      (node (ref "C19") (pin "1") (pintype "passive"))
      (node (ref "C20") (pin "1") (pintype "passive"))
      (node (ref "C22") (pin "2") (pintype "passive"))
      (node (ref "C24") (pin "2") (pintype "passive"))
      (node (ref "R15") (pin "1") (pintype "passive"))
    )
    (net (code "50") (name "/TX-") (class "Default")
      (node (ref "C12") (pin "2") (pintype "passive"))
      (node (ref "C13") (pin "2") (pintype "passive"))
      (node (ref "C8") (pin "2") (pintype "passive"))
      (node (ref "C9") (pin "2") (pintype "passive"))
      (node (ref "R11") (pin "1") (pintype "passive"))
      (node (ref "R7") (pin "1") (pinfunction "1_1") (pintype "passive"))
    )
    (net (code "51") (name "/TX0") (class "Default")
      (node (ref "J4") (pin "5") (pinfunction "5_5") (pintype "passive"))
      (node (ref "U5") (pin "1") (pinfunction "PORTA3/SDA1/I2SDIN/PWM3_P/SSPDIN/UTXD0/UTXD1/ANTCTL1/PDMD_AT/PWM2_N_1") (pintype "passive"))
    )
    (net (code "52") (name "/TXD") (class "Default")
      (node (ref "R19") (pin "2") (pinfunction "2_2") (pintype "passive"))
      (node (ref "U5") (pin "8") (pinfunction "PORTA5/SCL0/I2SCLK/PWM4_P/SSPCLK/URXD0/URXD1/CLKOUT/PDMC_LK/PWM5_N_8") (pintype "passive"))
    )
    (net (code "53") (name "/VMID") (class "Default")
      (node (ref "C6") (pin "1") (pintype "passive"))
      (node (ref "R4") (pin "2") (pintype "passive"))
      (node (ref "U1") (pin "16") (pinfunction "VMID_16") (pintype "passive"))
    )
    (net (code "54") (name "3V3") (class "Default")
      (node (ref "C21") (pin "2") (pinfunction "2_2") (pintype "passive"))
      (node (ref "C3") (pin "2") (pinfunction "2_2") (pintype "passive"))
      (node (ref "C4") (pin "2") (pinfunction "2_2") (pintype "passive"))
      (node (ref "C43") (pin "1") (pinfunction "1_1") (pintype "passive"))
      (node (ref "C44") (pin "1") (pinfunction "1_1") (pintype "passive"))
      (node (ref "C45") (pin "1") (pinfunction "1_1") (pintype "passive"))
      (node (ref "C46") (pin "2") (pinfunction "2_2") (pintype "passive"))
      (node (ref "C5") (pin "2") (pinfunction "2_2") (pintype "passive"))
      (node (ref "C52") (pin "1") (pinfunction "1_1") (pintype "passive"))
      (node (ref "J6") (pin "1") (pinfunction "1_1") (pintype "passive"))
      (node (ref "L2") (pin "1") (pintype "passive"))
      (node (ref "L6") (pin "1") (pintype "passive"))
      (node (ref "L9") (pin "2") (pintype "passive"))
      (node (ref "Q4") (pin "2") (pinfunction "S_2") (pintype "passive"))
      (node (ref "R1") (pin "2") (pinfunction "2_2") (pintype "passive"))
      (node (ref "R2") (pin "2") (pinfunction "2_2") (pintype "passive"))
      (node (ref "R3") (pin "2") (pinfunction "2_2") (pintype "passive"))
      (node (ref "SW1") (pin "1") (pinfunction "1_1") (pintype "passive"))
      (node (ref "SW1") (pin "4") (pinfunction "4_4") (pintype "passive"))
      (node (ref "TVS1") (pin "2") (pinfunction "2_2") (pintype "passive"))
      (node (ref "U2") (pin "1") (pinfunction "VDD_1") (pintype "passive"))
      (node (ref "U2") (pin "21") (pinfunction "CTRL_21") (pintype "passive"))
      (node (ref "U3") (pin "3") (pinfunction "Vout_3") (pintype "passive"))
      (node (ref "U5") (pin "20") (pinfunction "VBAT_20") (pintype "passive"))
    )
    (net (code "55") (name "3V3_SW") (class "Default")
      (node (ref "C38") (pin "2") (pinfunction "2_2") (pintype "passive"))
      (node (ref "C39") (pin "1") (pinfunction "1_1") (pintype "passive"))
      (node (ref "C53") (pin "1") (pinfunction "1_1") (pintype "passive"))
      (node (ref "J3") (pin "4") (pinfunction "4_4") (pintype "passive"))
      (node (ref "L1") (pin "1") (pintype "passive"))
      (node (ref "Q4") (pin "3") (pinfunction "D_3") (pintype "passive"))
    )
    (net (code "56") (name "6V_SW") (class "Default")
      (node (ref "C25") (pin "1") (pinfunction "1_1") (pintype "passive"))
      (node (ref "C48") (pin "1") (pinfunction "1_1") (pintype "passive"))
      (node (ref "L8") (pin "1") (pintype "passive"))
      (node (ref "Q2") (pin "3") (pinfunction "D_3") (pintype "passive"))
      (node (ref "R38") (pin "1") (pinfunction "1_1") (pintype "passive"))
      (node (ref "R40") (pin "1") (pinfunction "1_1") (pintype "passive"))
      (node (ref "U4") (pin "5") (pinfunction "VDD_5") (pintype "passive"))
    )
    (net (code "57") (name "DVDD") (class "Default")
      (node (ref "C1") (pin "1") (pinfunction "1_1") (pintype "passive"))
      (node (ref "C2") (pin "2") (pintype "passive"))
      (node (ref "C26") (pin "2") (pintype "passive"))
      (node (ref "C27") (pin "2") (pintype "passive"))
      (node (ref "C28") (pin "2") (pintype "passive"))
      (node (ref "D1") (pin "1") (pinfunction "K_1") (pintype "passive"))
      (node (ref "L1") (pin "2") (pintype "passive"))
      (node (ref "L2") (pin "2") (pintype "passive"))
      (node (ref "R14") (pin "1") (pintype "passive"))
      (node (ref "R16") (pin "1") (pinfunction "1_1") (pintype "passive"))
      (node (ref "R9") (pin "1") (pintype "passive"))
      (node (ref "U1") (pin "12") (pinfunction "TVDD_12") (pintype "passive"))
      (node (ref "U1") (pin "15") (pinfunction "AVDD_15") (pintype "passive"))
      (node (ref "U1") (pin "2") (pinfunction "PVDD_2") (pintype "passive"))
      (node (ref "U1") (pin "3") (pinfunction "DVDD_3") (pintype "passive"))
      (node (ref "U1") (pin "9") (pinfunction "SVDD_9") (pintype "passive"))
    )
    (net (code "58") (name "F_VCC") (class "Default")
      (node (ref "J3") (pin "6") (pinfunction "6_6") (pintype "passive"))
      (node (ref "L10") (pin "2") (pintype "passive"))
      (node (ref "L6") (pin "2") (pintype "passive"))
    )
    (net (code "59") (name "GND") (class "Default")
      (node (ref "C1") (pin "2") (pinfunction "2_2") (pintype "passive"))
      (node (ref "C10") (pin "1") (pintype "passive"))
      (node (ref "C11") (pin "1") (pintype "passive"))
      (node (ref "C12") (pin "1") (pintype "passive"))
      (node (ref "C13") (pin "1") (pintype "passive"))
      (node (ref "C14") (pin "1") (pinfunction "1_1") (pintype "passive"))
      (node (ref "C15") (pin "2") (pinfunction "2_2") (pintype "passive"))
      (node (ref "C16") (pin "2") (pinfunction "2_2") (pintype "passive"))
      (node (ref "C17") (pin "2") (pintype "passive"))
      (node (ref "C18") (pin "2") (pintype "passive"))
      (node (ref "C19") (pin "2") (pintype "passive"))
      (node (ref "C2") (pin "1") (pintype "passive"))
      (node (ref "C20") (pin "2") (pintype "passive"))
      (node (ref "C21") (pin "1") (pinfunction "1_1") (pintype "passive"))
      (node (ref "C23") (pin "1") (pinfunction "1_1") (pintype "passive"))
      (node (ref "C26") (pin "1") (pintype "passive"))
      (node (ref "C27") (pin "1") (pintype "passive"))
      (node (ref "C28") (pin "1") (pintype "passive"))
      (node (ref "C29") (pin "2") (pinfunction "2_2") (pintype "passive"))
      (node (ref "C3") (pin "1") (pinfunction "1_1") (pintype "passive"))
      (node (ref "C30") (pin "2") (pinfunction "2_2") (pintype "passive"))
      (node (ref "C32") (pin "1") (pintype "passive"))
      (node (ref "C33") (pin "1") (pintype "passive"))
      (node (ref "C34") (pin "1") (pinfunction "1_1") (pintype "passive"))
      (node (ref "C35") (pin "2") (pinfunction "2_2") (pintype "passive"))
      (node (ref "C36") (pin "2") (pinfunction "2_2") (pintype "passive"))
      (node (ref "C37") (pin "2") (pinfunction "2_2") (pintype "passive"))
      (node (ref "C38") (pin "1") (pinfunction "1_1") (pintype "passive"))
      (node (ref "C39") (pin "2") (pinfunction "2_2") (pintype "passive"))
      (node (ref "C4") (pin "1") (pinfunction "1_1") (pintype "passive"))
      (node (ref "C40") (pin "1") (pinfunction "1_1") (pintype "passive"))
      (node (ref "C41") (pin "1") (pinfunction "1_1") (pintype "passive"))
      (node (ref "C42") (pin "2") (pinfunction "2_2") (pintype "passive"))
      (node (ref "C43") (pin "2") (pinfunction "2_2") (pintype "passive"))
      (node (ref "C44") (pin "2") (pinfunction "2_2") (pintype "passive"))
      (node (ref "C45") (pin "2") (pinfunction "2_2") (pintype "passive"))
      (node (ref "C46") (pin "1") (pinfunction "1_1") (pintype "passive"))
      (node (ref "C47") (pin "2") (pinfunction "2_2") (pintype "passive"))
      (node (ref "C48") (pin "2") (pinfunction "2_2") (pintype "passive"))
      (node (ref "C49") (pin "1") (pinfunction "1_1") (pintype "passive"))
      (node (ref "C5") (pin "1") (pinfunction "1_1") (pintype "passive"))
      (node (ref "C50") (pin "1") (pinfunction "1_1") (pintype "passive"))
      (node (ref "C51") (pin "2") (pinfunction "2_2") (pintype "passive"))
      (node (ref "C52") (pin "2") (pinfunction "2_2") (pintype "passive"))
      (node (ref "C53") (pin "2") (pinfunction "2_2") (pintype "passive"))
      (node (ref "C54") (pin "1") (pinfunction "1_1") (pintype "passive"))
      (node (ref "C55") (pin "2") (pinfunction "2_2") (pintype "passive"))
      (node (ref "C56") (pin "2") (pinfunction "2_2") (pintype "passive"))
      (node (ref "C57") (pin "1") (pinfunction "1_1") (pintype "passive"))
      (node (ref "C58") (pin "2") (pinfunction "2_2") (pintype "passive"))
      (node (ref "C6") (pin "2") (pintype "passive"))
      (node (ref "J1") (pin "2") (pinfunction "2_2") (pintype "passive"))
      (node (ref "J1") (pin "3") (pinfunction "3_3") (pintype "passive"))
      (node (ref "J1") (pin "4") (pinfunction "4_4") (pintype "passive"))
      (node (ref "J2") (pin "3") (pinfunction "3_3") (pintype "passive"))
      (node (ref "J2") (pin "4") (pinfunction "4_4") (pintype "passive"))
      (node (ref "J3") (pin "1") (pinfunction "1_1") (pintype "passive"))
      (node (ref "J3") (pin "7") (pinfunction "7_7") (pintype "passive"))
      (node (ref "J3") (pin "8") (pinfunction "8_8") (pintype "passive"))
      (node (ref "J4") (pin "2") (pinfunction "2_2") (pintype "passive"))
      (node (ref "J6") (pin "4") (pinfunction "4_4") (pintype "passive"))
      (node (ref "Q3") (pin "2") (pinfunction "E_2") (pintype "passive"))
      (node (ref "R12") (pin "1") (pintype "passive"))
      (node (ref "R13") (pin "1") (pintype "passive"))
      (node (ref "R17") (pin "1") (pinfunction "1_1") (pintype "passive"))
      (node (ref "R24") (pin "2") (pinfunction "2_2") (pintype "passive"))
      (node (ref "R26") (pin "2") (pinfunction "2_2") (pintype "passive"))
      (node (ref "R27") (pin "2") (pinfunction "2_2") (pintype "passive"))
      (node (ref "R33") (pin "2") (pinfunction "2_2") (pintype "passive"))
      (node (ref "R39") (pin "2") (pinfunction "2_2") (pintype "passive"))
      (node (ref "R8") (pin "1") (pintype "passive"))
      (node (ref "TVS1") (pin "1") (pinfunction "1_1") (pintype "passive"))
      (node (ref "TVS3") (pin "1") (pinfunction "1_1") (pintype "passive"))
      (node (ref "U1") (pin "10") (pinfunction "TVss_10") (pintype "passive"))
      (node (ref "U1") (pin "14") (pinfunction "TVss_14") (pintype "passive"))
      (node (ref "U1") (pin "18") (pinfunction "AVSS_18") (pintype "passive"))
      (node (ref "U1") (pin "19") (pinfunction "AUX1_19") (pintype "passive"))
      (node (ref "U1") (pin "20") (pinfunction "AUX2_20") (pintype "passive"))
      (node (ref "U1") (pin "28") (pinfunction "D4/ADR_2_28") (pintype "passive"))
      (node (ref "U1") (pin "33") (pinfunction "Thermal_Pad_33") (pintype "passive"))
      (node (ref "U1") (pin "4") (pinfunction "DVSS_4") (pintype "passive"))
      (node (ref "U1") (pin "5") (pinfunction "PVSS_5") (pintype "passive"))
      (node (ref "U1") (pin "7") (pinfunction "MFIN_7") (pintype "passive"))
      (node (ref "U2") (pin "17") (pinfunction "GND_17") (pintype "passive"))
      (node (ref "U2") (pin "25") (pinfunction "G_25") (pintype "passive"))
      (node (ref "U3") (pin "1") (pinfunction "GND_1") (pintype "passive"))
      (node (ref "U4") (pin "2") (pinfunction "GND_2") (pintype "passive"))
      (node (ref "U5") (pin "10") (pinfunction "GND_10") (pintype "passive"))
      (node (ref "U5") (pin "49") (pinfunction "GND_PADDLE_49") (pintype "passive"))
      (node (ref "X1") (pin "3") (pintype "passive"))
      (node (ref "X1") (pin "4") (pintype "passive"))
      (node (ref "X2") (pin "3") (pintype "passive"))
      (node (ref "X2") (pin "4") (pintype "passive"))
      (node (ref "Y1") (pin "2") (pintype "passive"))
      (node (ref "Y1") (pin "4") (pintype "passive"))
    )
    (net (code "60") (name "Net-(C7-Pad2)") (class "Default")
      (node (ref "C7") (pin "2") (pintype "passive"))
      (node (ref "R10") (pin "1") (pintype "passive"))
      (node (ref "R5") (pin "2") (pintype "passive"))
    )
    (net (code "61") (name "Net-(C10-Pad2)") (class "Default")
      (node (ref "C10") (pin "2") (pintype "passive"))
      (node (ref "C11") (pin "2") (pintype "passive"))
      (node (ref "C8") (pin "1") (pintype "passive"))
      (node (ref "C9") (pin "1") (pintype "passive"))
      (node (ref "L3") (pin "2") (pintype "passive"))
      (node (ref "R10") (pin "2") (pintype "passive"))
      (node (ref "R6") (pin "1") (pinfunction "1_1") (pintype "passive"))
    )
    (net (code "62") (name "Net-(C17-Pad1)") (class "Default")
      (node (ref "C17") (pin "1") (pintype "passive"))
      (node (ref "C18") (pin "1") (pintype "passive"))
      (node (ref "C22") (pin "1") (pintype "passive"))
      (node (ref "C24") (pin "1") (pintype "passive"))
      (node (ref "L4") (pin "2") (pintype "passive"))
    )
    (net (code "63") (name "Net-(C58-Pad1)") (class "Default")
      (node (ref "C58") (pin "1") (pinfunction "1_1") (pintype "passive"))
      (node (ref "LED#1") (pin "1") (pintype "passive"))
      (node (ref "LED*1") (pin "1") (pintype "passive"))
      (node (ref "LED1") (pin "1") (pintype "passive"))
      (node (ref "LED10") (pin "1") (pintype "passive"))
      (node (ref "LED2") (pin "1") (pintype "passive"))
      (node (ref "LED3") (pin "1") (pintype "passive"))
      (node (ref "LED4") (pin "1") (pintype "passive"))
      (node (ref "LED5") (pin "1") (pintype "passive"))
      (node (ref "LED6") (pin "1") (pintype "passive"))
      (node (ref "LED7") (pin "1") (pintype "passive"))
      (node (ref "LED8") (pin "1") (pintype "passive"))
      (node (ref "LED9") (pin "1") (pintype "passive"))
      (node (ref "R40") (pin "2") (pinfunction "2_2") (pintype "passive"))
    )
    (net (code "64") (name "Net-(D1-A)") (class "Default")
      (node (ref "C23") (pin "2") (pinfunction "2_2") (pintype "passive"))
      (node (ref "D1") (pin "2") (pinfunction "A_2") (pintype "passive"))
      (node (ref "R14") (pin "2") (pintype "passive"))
      (node (ref "U1") (pin "6") (pinfunction "NRSTPD_6") (pintype "passive"))
    )
    (net (code "65") (name "Net-(J3-Pad2)") (class "Default")
      (node (ref "J3") (pin "2") (pinfunction "2_2") (pintype "passive"))
      (node (ref "R19") (pin "1") (pinfunction "1_1") (pintype "passive"))
    )
    (net (code "66") (name "Net-(J3-Pad3)") (class "Default")
      (node (ref "J3") (pin "3") (pinfunction "3_3") (pintype "passive"))
      (node (ref "R20") (pin "1") (pinfunction "1_1") (pintype "passive"))
    )
    (net (code "67") (name "Net-(J3-Pad5)") (class "Default")
      (node (ref "J3") (pin "5") (pinfunction "5_5") (pintype "passive"))
      (node (ref "R22") (pin "2") (pinfunction "2_2") (pintype "passive"))
    )
    (net (code "68") (name "Net-(J4-Pad3)") (class "Default")
      (node (ref "J4") (pin "3") (pinfunction "3_3") (pintype "passive"))
      (node (ref "R25") (pin "2") (pinfunction "2_2") (pintype "passive"))
    )
    (net (code "69") (name "Net-(LED#1-Pad2)") (class "Default")
      (node (ref "LED#1") (pin "2") (pintype "passive"))
      (node (ref "R29") (pin "2") (pinfunction "2_2") (pintype "passive"))
    )
    (net (code "70") (name "Net-(LED*1-Pad2)") (class "Default")
      (node (ref "LED*1") (pin "2") (pintype "passive"))
      (node (ref "R32") (pin "2") (pinfunction "2_2") (pintype "passive"))
    )
    (net (code "71") (name "Net-(LED1-Pad2)") (class "Default")
      (node (ref "LED1") (pin "2") (pintype "passive"))
      (node (ref "LED2") (pin "2") (pintype "passive"))
      (node (ref "LED3") (pin "2") (pintype "passive"))
      (node (ref "R37") (pin "2") (pinfunction "2_2") (pintype "passive"))
    )
    (net (code "72") (name "Net-(LED4-Pad2)") (class "Default")
      (node (ref "LED4") (pin "2") (pintype "passive"))
      (node (ref "LED6") (pin "2") (pintype "passive"))
      (node (ref "R36") (pin "2") (pinfunction "2_2") (pintype "passive"))
    )
    (net (code "73") (name "Net-(LED5-Pad2)") (class "Default")
      (node (ref "LED5") (pin "2") (pintype "passive"))
      (node (ref "R35") (pin "2") (pinfunction "2_2") (pintype "passive"))
    )
    (net (code "74") (name "Net-(LED7-Pad2)") (class "Default")
      (node (ref "LED7") (pin "2") (pintype "passive"))
      (node (ref "LED8") (pin "2") (pintype "passive"))
      (node (ref "LED9") (pin "2") (pintype "passive"))
      (node (ref "R34") (pin "2") (pinfunction "2_2") (pintype "passive"))
    )
    (net (code "75") (name "Net-(LED10-Pad2)") (class "Default")
      (node (ref "LED10") (pin "2") (pintype "passive"))
      (node (ref "R31") (pin "2") (pinfunction "2_2") (pintype "passive"))
    )
    (net (code "76") (name "Net-(Q1-G)") (class "Default")
      (node (ref "C31") (pin "2") (pinfunction "2_2") (pintype "passive"))
      (node (ref "Q1") (pin "1") (pinfunction "G_1") (pintype "passive"))
      (node (ref "R17") (pin "2") (pinfunction "2_2") (pintype "passive"))
    )
    (net (code "77") (name "Net-(Q3-B)") (class "Default")
      (node (ref "Q3") (pin "1") (pinfunction "B_1") (pintype "passive"))
      (node (ref "R30") (pin "2") (pinfunction "2_2") (pintype "passive"))
      (node (ref "R33") (pin "1") (pinfunction "1_1") (pintype "passive"))
    )
    (net (code "78") (name "Net-(R5-Pad1)") (class "Default")
      (node (ref "R5") (pin "1") (pintype "passive"))
      (node (ref "R6") (pin "2") (pinfunction "2_2") (pintype "passive"))
      (node (ref "R7") (pin "2") (pinfunction "2_2") (pintype "passive"))
    )
    (net (code "79") (name "Net-(R11-Pad2)") (class "Default")
      (node (ref "R11") (pin "2") (pintype "passive"))
      (node (ref "R15") (pin "2") (pintype "passive"))
    )
    (net (code "80") (name "Net-(U1-D5{slash}ADR_1{slash}SCK{slash}DTRQ)") (class "Default")
      (node (ref "R12") (pin "2") (pintype "passive"))
      (node (ref "U1") (pin "29") (pinfunction "D5/ADR_1/SCK/DTRQ_29") (pintype "passive"))
    )
    (net (code "81") (name "Net-(U1-D6{slash}ADR_0{slash}MOSI{slash}MX)") (class "Default")
      (node (ref "R13") (pin "2") (pintype "passive"))
      (node (ref "U1") (pin "30") (pinfunction "D6/ADR_0/MOSI/MX_30") (pintype "passive"))
    )
    (net (code "82") (name "Net-(U1-OSCIN)") (class "Default")
      (node (ref "C33") (pin "2") (pintype "passive"))
      (node (ref "U1") (pin "21") (pinfunction "OSCIN_21") (pintype "passive"))
      (node (ref "Y1") (pin "3") (pintype "passive"))
    )
    (net (code "83") (name "Net-(U1-OSCOUT)") (class "Default")
      (node (ref "C32") (pin "2") (pintype "passive"))
      (node (ref "U1") (pin "22") (pinfunction "OSCOUT_22") (pintype "passive"))
      (node (ref "Y1") (pin "1") (pintype "passive"))
    )
    (net (code "84") (name "Net-(U1-RX)") (class "Default")
      (node (ref "C7") (pin "1") (pintype "passive"))
      (node (ref "R4") (pin "1") (pintype "passive"))
      (node (ref "U1") (pin "17") (pinfunction "RX_17") (pintype "passive"))
    )
    (net (code "85") (name "Net-(U1-TX1)") (class "Default")
      (node (ref "L3") (pin "1") (pintype "passive"))
      (node (ref "U1") (pin "11") (pinfunction "TX1_11") (pintype "passive"))
    )
    (net (code "86") (name "Net-(U1-TX2)") (class "Default")
      (node (ref "L4") (pin "1") (pintype "passive"))
      (node (ref "U1") (pin "13") (pinfunction "TX2_13") (pintype "passive"))
    )
    (net (code "87") (name "Net-(U2-RIN)") (class "Default")
      (node (ref "C14") (pin "2") (pinfunction "2_2") (pintype "passive"))
      (node (ref "U2") (pin "18") (pinfunction "RIN_18") (pintype "passive"))
    )
    (net (code "88") (name "Net-(U2-SIN1)") (class "Default")
      (node (ref "RN1") (pin "4") (pinfunction "4_4") (pintype "passive"))
      (node (ref "U2") (pin "2") (pinfunction "SIN1_2") (pintype "passive"))
    )
    (net (code "89") (name "Net-(U2-SIN2)") (class "Default")
      (node (ref "RN1") (pin "3") (pinfunction "3_3") (pintype "passive"))
      (node (ref "U2") (pin "3") (pinfunction "SIN2_3") (pintype "passive"))
    )
    (net (code "90") (name "Net-(U2-SIN3)") (class "Default")
      (node (ref "RN1") (pin "2") (pinfunction "2_2") (pintype "passive"))
      (node (ref "U2") (pin "4") (pinfunction "SIN3_4") (pintype "passive"))
    )
    (net (code "91") (name "Net-(U2-SIN4)") (class "Default")
      (node (ref "RN1") (pin "1") (pinfunction "1_1") (pintype "passive"))
      (node (ref "U2") (pin "5") (pinfunction "SIN4_5") (pintype "passive"))
    )
    (net (code "92") (name "Net-(U2-SIN5)") (class "Default")
      (node (ref "RN2") (pin "4") (pinfunction "4_4") (pintype "passive"))
      (node (ref "U2") (pin "6") (pinfunction "SIN5_6") (pintype "passive"))
    )
    (net (code "93") (name "Net-(U2-SIN6)") (class "Default")
      (node (ref "RN2") (pin "3") (pinfunction "3_3") (pintype "passive"))
      (node (ref "U2") (pin "7") (pinfunction "SIN6_7") (pintype "passive"))
    )
    (net (code "94") (name "Net-(U2-SIN7)") (class "Default")
      (node (ref "RN2") (pin "2") (pinfunction "2_2") (pintype "passive"))
      (node (ref "U2") (pin "8") (pinfunction "SIN7_8") (pintype "passive"))
    )
    (net (code "95") (name "Net-(U2-SIN8)") (class "Default")
      (node (ref "RN2") (pin "1") (pinfunction "1_1") (pintype "passive"))
      (node (ref "U2") (pin "9") (pinfunction "SIN8_9") (pintype "passive"))
    )
    (net (code "96") (name "Net-(U2-SIN9)") (class "Default")
      (node (ref "RN3") (pin "4") (pinfunction "4_4") (pintype "passive"))
      (node (ref "U2") (pin "10") (pinfunction "SIN9_10") (pintype "passive"))
    )
    (net (code "97") (name "Net-(U2-SIN10)") (class "Default")
      (node (ref "RN3") (pin "3") (pinfunction "3_3") (pintype "passive"))
      (node (ref "U2") (pin "11") (pinfunction "SIN10_11") (pintype "passive"))
    )
    (net (code "98") (name "Net-(U2-SIN11)") (class "Default")
      (node (ref "RN3") (pin "2") (pinfunction "2_2") (pintype "passive"))
      (node (ref "U2") (pin "13") (pinfunction "SIN11_13") (pintype "passive"))
    )
    (net (code "99") (name "Net-(U2-SIN12)") (class "Default")
      (node (ref "RN3") (pin "1") (pinfunction "1_1") (pintype "passive"))
      (node (ref "U2") (pin "14") (pinfunction "SIN12_14") (pintype "passive"))
    )
    (net (code "100") (name "Net-(U5-BFB)") (class "Default")
      (node (ref "C49") (pin "2") (pinfunction "2_2") (pintype "passive"))
      (node (ref "C50") (pin "2") (pinfunction "2_2") (pintype "passive"))
      (node (ref "L11") (pin "1") (pinfunction "1_1") (pintype "passive"))
      (node (ref "U5") (pin "22") (pinfunction "BFB_22") (pintype "passive"))
    )
    (net (code "101") (name "Net-(U5-BSW)") (class "Default")
      (node (ref "L11") (pin "2") (pinfunction "2_2") (pintype "passive"))
      (node (ref "U5") (pin "21") (pinfunction "BSW_21") (pintype "passive"))
    )
    (net (code "102") (name "Net-(U5-MIC_BIAS)") (class "Default")
      (node (ref "C36") (pin "1") (pinfunction "1_1") (pintype "passive"))
      (node (ref "U5") (pin "13") (pinfunction "MIC_BIAS_13") (pintype "passive"))
    )
    (net (code "103") (name "Net-(U5-MIC_IN)") (class "Default")
      (node (ref "TP1") (pin "1") (pinfunction "1_1") (pintype "passive"))
      (node (ref "U5") (pin "14") (pinfunction "MIC_IN_14") (pintype "passive"))
    )
    (net (code "104") (name "Net-(U5-VCHG)") (class "Default")
      (node (ref "C42") (pin "1") (pinfunction "1_1") (pintype "passive"))
      (node (ref "U5") (pin "19") (pinfunction "VCHG_19") (pintype "passive"))
    )
    (net (code "105") (name "Net-(U5-VMID)") (class "Default")
      (node (ref "C37") (pin "1") (pinfunction "1_1") (pintype "passive"))
      (node (ref "U5") (pin "15") (pinfunction "VMID_15") (pintype "passive"))
    )
    (net (code "106") (name "Net-(U5-XTALI_24M)") (class "Default")
      (node (ref "C41") (pin "2") (pinfunction "2_2") (pintype "passive"))
      (node (ref "U5") (pin "12") (pinfunction "XTALI_24M_12") (pintype "passive"))
      (node (ref "X1") (pin "1") (pintype "passive"))
    )
    (net (code "107") (name "Net-(U5-XTALI_32K)") (class "Default")
      (node (ref "C54") (pin "2") (pinfunction "2_2") (pintype "passive"))
      (node (ref "U5") (pin "24") (pinfunction "XTALI_32K_24") (pintype "passive"))
      (node (ref "X2") (pin "2") (pintype "passive"))
    )
    (net (code "108") (name "Net-(U5-XTALO_24M)") (class "Default")
      (node (ref "C40") (pin "2") (pinfunction "2_2") (pintype "passive"))
      (node (ref "U5") (pin "11") (pinfunction "XTALO_24M_11") (pintype "passive"))
      (node (ref "X1") (pin "2") (pintype "passive"))
    )
    (net (code "109") (name "Net-(U5-XTALO_32K)") (class "Default")
      (node (ref "C57") (pin "2") (pinfunction "2_2") (pintype "passive"))
      (node (ref "U5") (pin "25") (pinfunction "XTALO_32K_25") (pintype "passive"))
      (node (ref "X2") (pin "1") (pintype "passive"))
    )
    (net (code "110") (name "RF_PW") (class "Default")
      (node (ref "C35") (pin "1") (pinfunction "1_1") (pintype "passive"))
      (node (ref "J4") (pin "7") (pinfunction "7_7") (pintype "passive"))
      (node (ref "L8") (pin "2") (pintype "passive"))
      (node (ref "L9") (pin "1") (pintype "passive"))
      (node (ref "R18") (pin "2") (pinfunction "2_2") (pintype "passive"))
    )
    (net (code "111") (name "VBAT") (class "Default")
      (node (ref "J4") (pin "1") (pinfunction "1_1") (pintype "passive"))
      (node (ref "Q1") (pin "2") (pinfunction "S_2") (pintype "passive"))
      (node (ref "VD1") (pin "2") (pinfunction "K_2") (pintype "passive"))
    )
    (net (code "112") (name "VDDIO") (class "Default")
      (node (ref "C51") (pin "1") (pinfunction "1_1") (pintype "passive"))
      (node (ref "U5") (pin "23") (pinfunction "LDO_OUT_23") (pintype "passive"))
    )
    (net (code "113") (name "VIN") (class "Default")
      (node (ref "C30") (pin "1") (pinfunction "1_1") (pintype "passive"))
      (node (ref "C31") (pin "1") (pinfunction "1_1") (pintype "passive"))
      (node (ref "J1") (pin "1") (pinfunction "1_1") (pintype "passive"))
      (node (ref "TVS3") (pin "2") (pinfunction "2_2") (pintype "passive"))
      (node (ref "VD1") (pin "1") (pinfunction "A_1") (pintype "passive"))
    )
    (net (code "114") (name "V_POW") (class "Default")
      (node (ref "C15") (pin "1") (pinfunction "1_1") (pintype "passive"))
      (node (ref "C16") (pin "1") (pinfunction "1_1") (pintype "passive"))
      (node (ref "C29") (pin "1") (pinfunction "1_1") (pintype "passive"))
      (node (ref "C47") (pin "1") (pinfunction "1_1") (pintype "passive"))
      (node (ref "L10") (pin "1") (pintype "passive"))
      (node (ref "Q1") (pin "3") (pinfunction "D_3") (pintype "passive"))
      (node (ref "Q2") (pin "2") (pinfunction "S_2") (pintype "passive"))
      (node (ref "R28") (pin "1") (pinfunction "1_1") (pintype "passive"))
      (node (ref "U3") (pin "2") (pinfunction "Vin_2") (pintype "passive"))
    )
    (net (code "115") (name "unconnected-(ANT1-Pad2)") (class "Default")
      (node (ref "ANT1") (pin "2") (pintype "passive"))
    )
    (net (code "116") (name "unconnected-(C25-Pad2)") (class "Default")
      (node (ref "C25") (pin "2") (pinfunction "2_2") (pintype "passive"))
    )
    (net (code "117") (name "unconnected-(SW1-Pad3)") (class "Default")
      (node (ref "SW1") (pin "3") (pinfunction "3_3") (pintype "passive+no_connect"))
    )
    (net (code "118") (name "unconnected-(SW1-Pad6)") (class "Default")
      (node (ref "SW1") (pin "6") (pinfunction "6_6") (pintype "passive+no_connect"))
    )
    (net (code "119") (name "unconnected-(U1-D1{slash}ADR_5-Pad25)") (class "Default")
      (node (ref "U1") (pin "25") (pinfunction "D1/ADR_5_25") (pintype "passive"))
    )
    (net (code "120") (name "unconnected-(U1-D2{slash}ADR_4-Pad26)") (class "Default")
      (node (ref "U1") (pin "26") (pinfunction "D2/ADR_4_26") (pintype "passive"))
    )
    (net (code "121") (name "unconnected-(U1-D3{slash}ADR_3-Pad27)") (class "Default")
      (node (ref "U1") (pin "27") (pinfunction "D3/ADR_3_27") (pintype "passive"))
    )
    (net (code "122") (name "unconnected-(U1-MFOUT-Pad8)") (class "Default")
      (node (ref "U1") (pin "8") (pinfunction "MFOUT_8") (pintype "passive"))
    )
    (net (code "123") (name "unconnected-(U2-NC-Pad12)") (class "Default")
      (node (ref "U2") (pin "12") (pinfunction "NC_12") (pintype "passive+no_connect"))
    )
    (net (code "124") (name "unconnected-(U2-NC-Pad20)") (class "Default")
      (node (ref "U2") (pin "20") (pinfunction "NC_20") (pintype "passive+no_connect"))
    )
    (net (code "125") (name "unconnected-(U2-NRST-Pad19)") (class "Default")
      (node (ref "U2") (pin "19") (pinfunction "NRST_19") (pintype "passive+no_connect"))
    )
    (net (code "126") (name "unconnected-(U2-SIN13-Pad15)") (class "Default")
      (node (ref "U2") (pin "15") (pinfunction "SIN13_15") (pintype "passive+no_connect"))
    )
    (net (code "127") (name "unconnected-(U2-SIN14-Pad16)") (class "Default")
      (node (ref "U2") (pin "16") (pinfunction "SIN14_16") (pintype "passive"))
    )
    (net (code "128") (name "unconnected-(U5-N{slash}A-Pad33)") (class "Default")
      (node (ref "U5") (pin "33") (pinfunction "N/A_33") (pintype "passive+no_connect"))
    )
    (net (code "129") (name "unconnected-(U5-PORTB7{slash}SDA1{slash}I2SDIN{slash}PWM3_P{slash}SSPDIN{slash}UTXD0{slash}UTXD1{slash}CLKOUT{slash}PDMD_AT{slash}PWM2_N-Pad44)") (class "Default")
      (node (ref "U5") (pin "44") (pinfunction "PORTB7/SDA1/I2SDIN/PWM3_P/SSPDIN/UTXD0/UTXD1/CLKOUT/PDMD_AT/PWM2_N_44") (pintype "passive"))
    )
    (net (code "130") (name "unconnected-(U5-PORTC1{slash}SDA0{slash}I2SFRM{slash}PWM1_P{slash}SSPCSN{slash}UTXD0{slash}UTXD1{slash}SWV{slash}PDMDAT{slash}_PWM0_N-Pad36)") (class "Default")
      (node (ref "U5") (pin "36") (pinfunction "PORTC1/SDA0/I2SFRM/PWM1_P/SSPCSN/UTXD0/UTXD1/SWV/PDMDAT/_PWM0_N_36") (pintype "passive"))
    )
    (net (code "131") (name "unconnected-(U5-PORTC2{slash}SCL1{slash}I2SDOUT{slash}PWM2_P{slash}SSPDOUT{slash}URXD0{slash}URXD1{slash}SWV{slash}PDMCL_K{slash}PWM3_N-Pad35)") (class "Default")
      (node (ref "U5") (pin "35") (pinfunction "PORTC2/SCL1/I2SDOUT/PWM2_P/SSPDOUT/URXD0/URXD1/SWV/PDMCL_K/PWM3_N_35") (pintype "passive"))
    )
    (net (code "132") (name "unconnected-(U5-PORTD3{slash}SDA1{slash}I2SDIN{slash}PWM3_P{slash}SSPDIN{slash}UTXD0{slash}UTXD1{slash}WLANRX{slash}PDMD_AT{slash}PWM2_N-Pad38)") (class "Default")
      (node (ref "U5") (pin "38") (pinfunction "PORTD3/SDA1/I2SDIN/PWM3_P/SSPDIN/UTXD0/UTXD1/WLANRX/PDMD_AT/PWM2_N_38") (pintype "passive"))
    )
  )
)
